# ProPrj_5VBuck_MP2236_2024-12-14.net
KiCad netlist of a schematic drawn in EasyEDA Pro
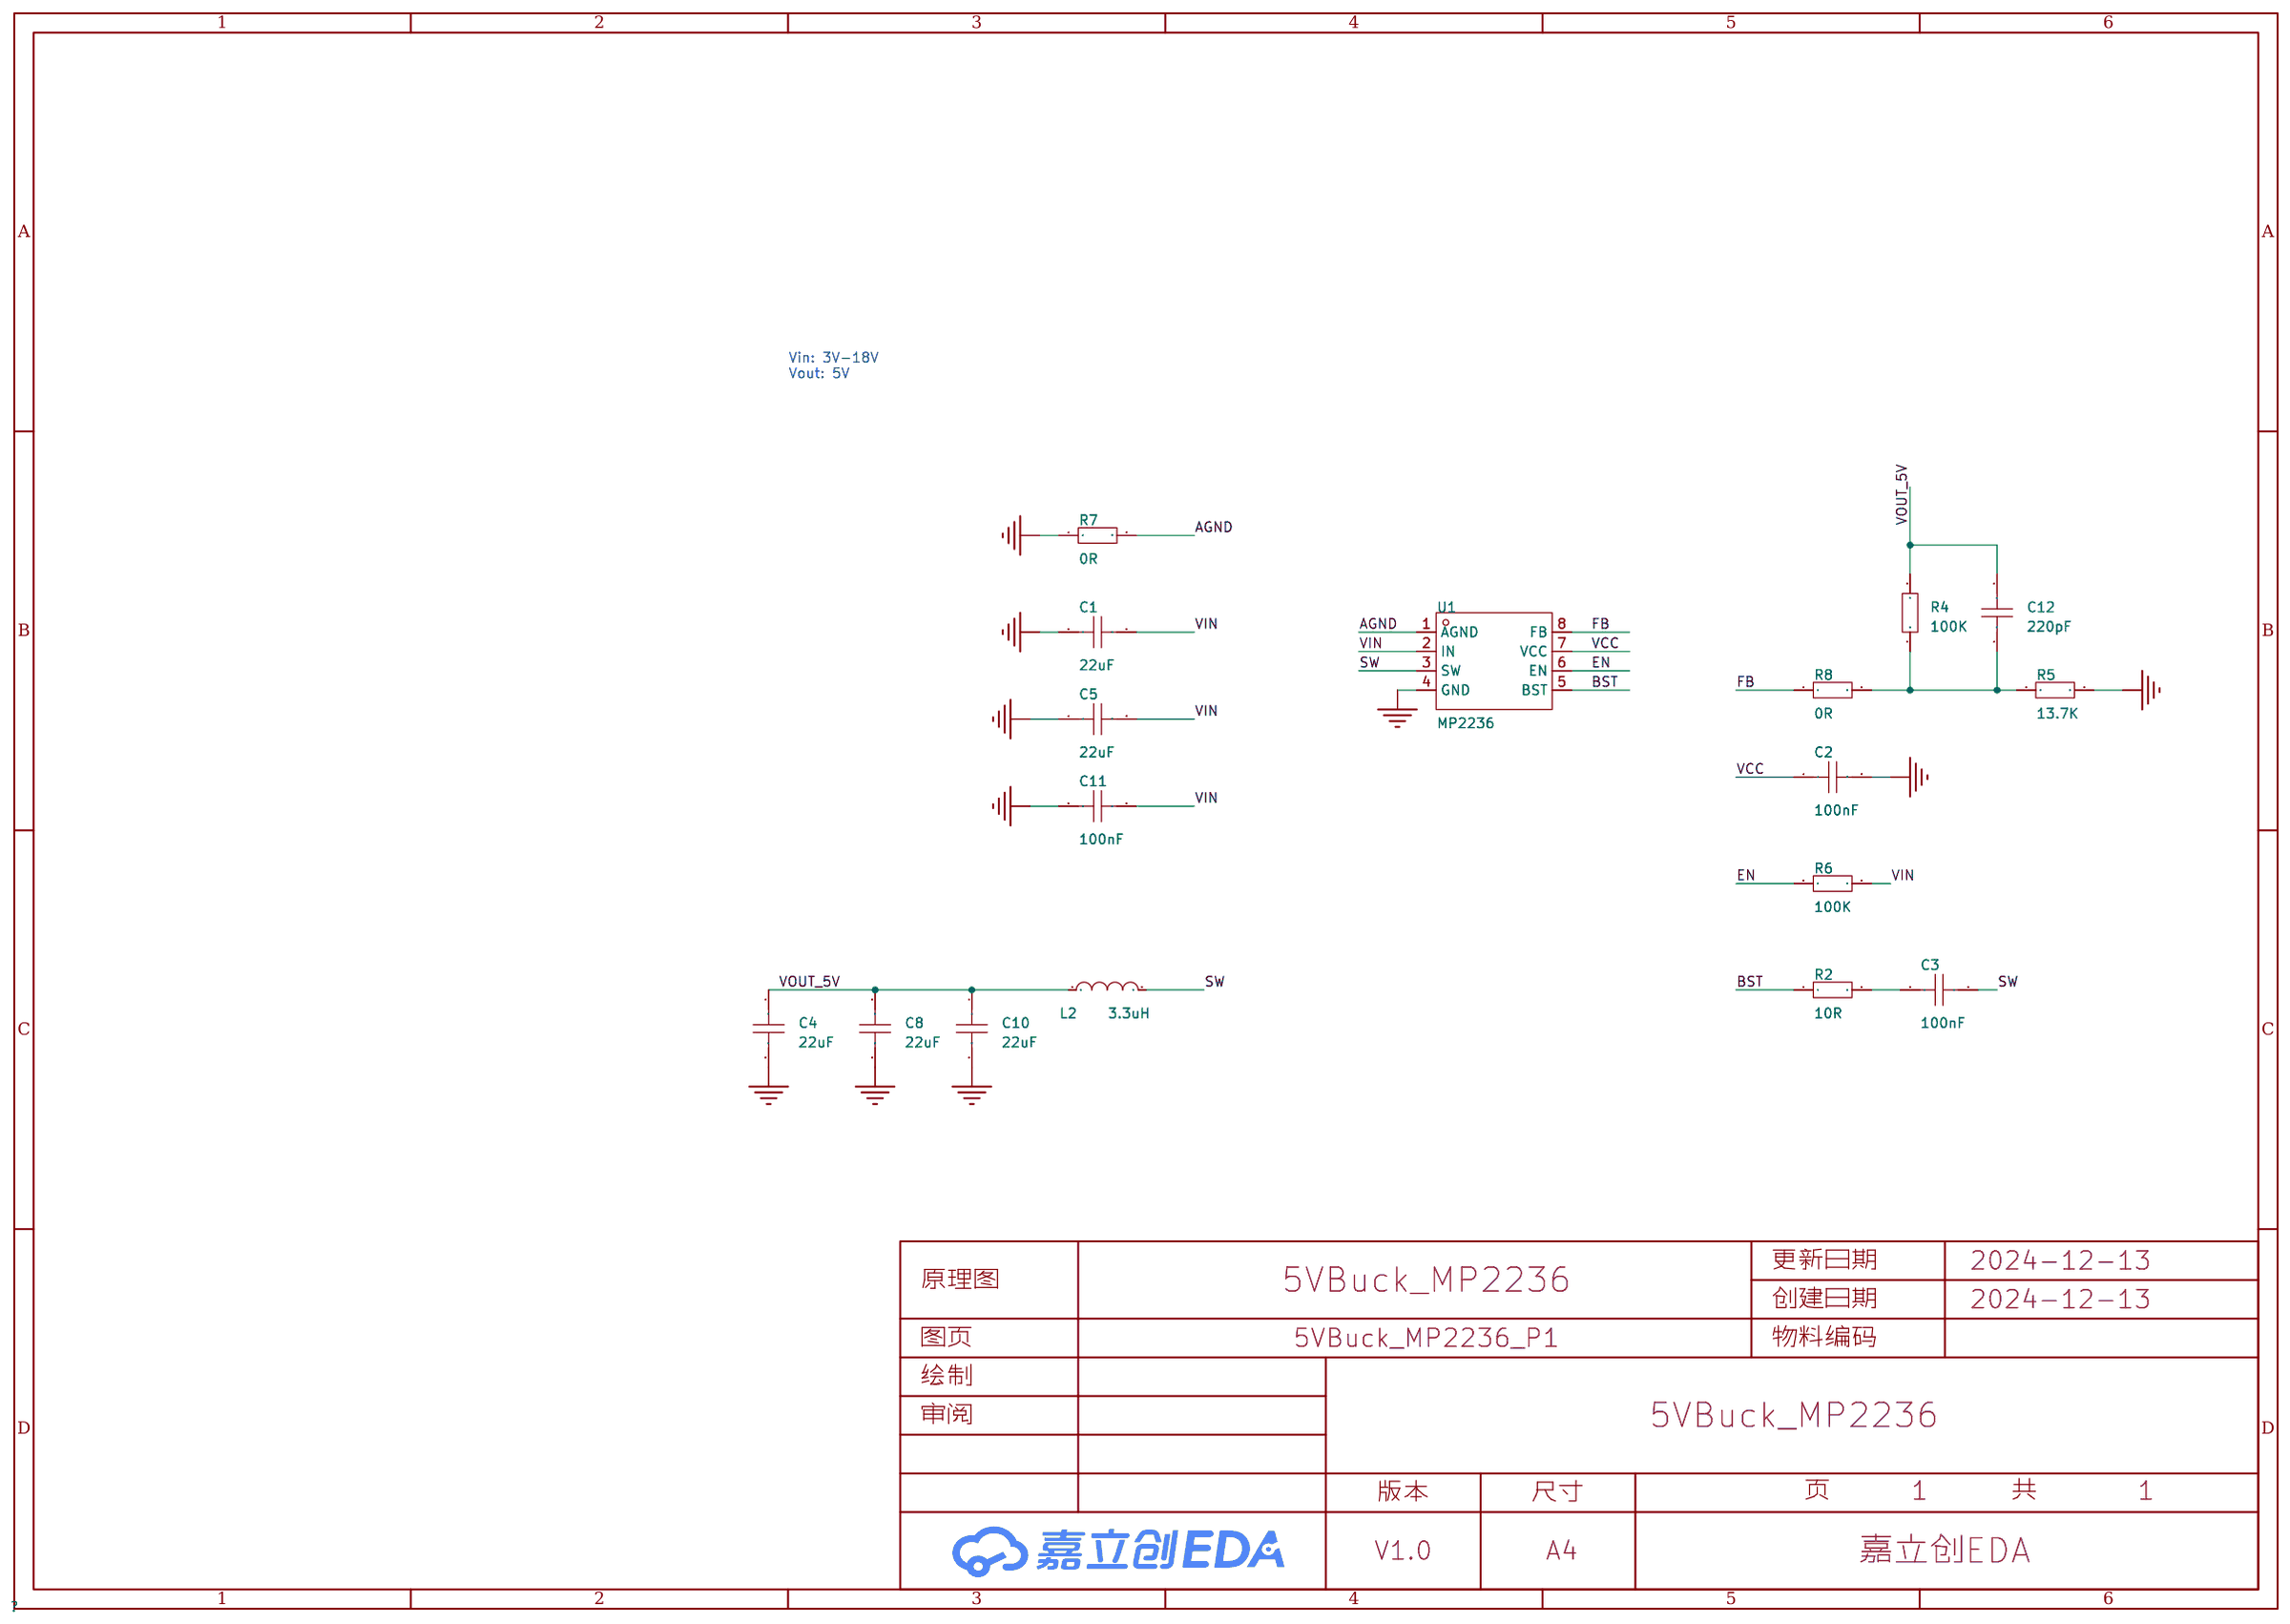
[diagram p0: schematic sheet]

(export (version "E")
  (design (tool "Eeschema 10.0.6"))
  (components
    (comp (ref "C1")
      (value "22uF")
      (footprint "easyedapro:C0805")
      (libsource (lib "easyedapro") (part "CapAcitance"))
    )
    (comp (ref "C2")
      (value "100nF")
      (footprint "easyedapro:C0805")
      (libsource (lib "easyedapro") (part "CapAcitance"))
    )
    (comp (ref "C3")
      (value "100nF")
      (footprint "easyedapro:C0805")
      (libsource (lib "easyedapro") (part "CapAcitance"))
    )
    (comp (ref "C4")
      (value "22uF")
      (footprint "easyedapro:C0805")
      (libsource (lib "easyedapro") (part "CapAcitance"))
    )
    (comp (ref "C5")
      (value "22uF")
      (footprint "easyedapro:C0805")
      (libsource (lib "easyedapro") (part "CapAcitance"))
    )
    (comp (ref "C8")
      (value "22uF")
      (footprint "easyedapro:C0805")
      (libsource (lib "easyedapro") (part "CapAcitance"))
    )
    (comp (ref "C10")
      (value "22uF")
      (footprint "easyedapro:C0805")
      (libsource (lib "easyedapro") (part "CapAcitance"))
    )
    (comp (ref "C11")
      (value "100nF")
      (footprint "easyedapro:C0805")
      (libsource (lib "easyedapro") (part "CapAcitance"))
    )
    (comp (ref "C12")
      (value "220pF")
      (footprint "easyedapro:C0805")
      (libsource (lib "easyedapro") (part "CapAcitance"))
    )
    (comp (ref "L2")
      (value "3.3uH")
      (footprint "easyedapro:IND-SMD_L7.1-W6.6_MJC-0603T")
      (description "电感值:5.6uH;精度:±20%;额定电流:5.5A;饱和电流(Isat):7A;类型:一体成型电感;")
      (fields
        (field (name "Manufacturer Part") "CXP0630-5R6M-AG(5.6uh)")
        (field (name "Manufacturer") "DMBJ(振宝佳)")
      )
      (libsource (lib "easyedapro") (part "CXP0630-5R6M-AG(5.6UH)"))
    )
    (comp (ref "R2") (value "10R") (footprint "easyedapro:R0805") (libsource (lib "easyedapro") (part "电阻")))
    (comp (ref "R4") (value "100K") (footprint "easyedapro:R0805") (libsource (lib "easyedapro") (part "电阻")))
    (comp (ref "R5")
      (value "13.7K")
      (footprint "easyedapro:R0805")
      (libsource (lib "easyedapro") (part "电阻"))
    )
    (comp (ref "R6") (value "100K") (footprint "easyedapro:R0805") (libsource (lib "easyedapro") (part "电阻")))
    (comp (ref "R7") (value "0R") (footprint "easyedapro:R0805") (libsource (lib "easyedapro") (part "电阻")))
    (comp (ref "R8") (value "0R") (footprint "easyedapro:R0805") (libsource (lib "easyedapro") (part "电阻")))
    (comp (ref "U1")
      (value "MP2236")
      (footprint "easyedapro:SOT-23-8_L3.0-W1.7-P0.65-LS2.8-BL")
      (libsource (lib "easyedapro") (part "MP2236"))
    )
  )
  (nets
    (net (code "1") (name "/AGND") (class "Default")
      (node (ref "R7") (pin "2") (pinfunction "2_2") (pintype "input"))
      (node (ref "U1") (pin "1") (pinfunction "AGND_1") (pintype "unspecified"))
    )
    (net (code "2") (name "/BST") (class "Default")
      (node (ref "R2") (pin "1") (pinfunction "1_1") (pintype "input"))
      (node (ref "U1") (pin "5") (pinfunction "BST_5") (pintype "unspecified"))
    )
    (net (code "3") (name "/EN") (class "Default")
      (node (ref "R6") (pin "2") (pinfunction "2_2") (pintype "input"))
      (node (ref "U1") (pin "6") (pinfunction "EN_6") (pintype "unspecified"))
    )
    (net (code "4") (name "/FB") (class "Default")
      (node (ref "R8") (pin "1") (pinfunction "1_1") (pintype "input"))
      (node (ref "U1") (pin "8") (pinfunction "FB_8") (pintype "unspecified"))
    )
    (net (code "5") (name "/SW") (class "Default")
      (node (ref "C3") (pin "2") (pinfunction "2_2") (pintype "input"))
      (node (ref "L2") (pin "2") (pinfunction "2_2") (pintype "unspecified"))
      (node (ref "U1") (pin "3") (pinfunction "SW_3") (pintype "unspecified"))
    )
    (net (code "6") (name "/VCC") (class "Default")
      (node (ref "C2") (pin "1") (pinfunction "1_1") (pintype "input"))
      (node (ref "U1") (pin "7") (pinfunction "VCC_7") (pintype "unspecified"))
    )
    (net (code "7") (name "/VIN") (class "Default")
      (node (ref "C1") (pin "2") (pinfunction "2_2") (pintype "input"))
      (node (ref "C11") (pin "2") (pinfunction "2_2") (pintype "input"))
      (node (ref "C5") (pin "2") (pinfunction "2_2") (pintype "input"))
      (node (ref "R6") (pin "1") (pinfunction "1_1") (pintype "input"))
      (node (ref "U1") (pin "2") (pinfunction "IN_2") (pintype "unspecified"))
    )
    (net (code "8") (name "/VOUT_5V") (class "Default")
      (node (ref "C10") (pin "1") (pinfunction "1_1") (pintype "input"))
      (node (ref "C12") (pin "2") (pinfunction "2_2") (pintype "input"))
      (node (ref "C4") (pin "1") (pinfunction "1_1") (pintype "input"))
      (node (ref "C8") (pin "1") (pinfunction "1_1") (pintype "input"))
      (node (ref "L2") (pin "1") (pinfunction "1_1") (pintype "unspecified"))
      (node (ref "R4") (pin "2") (pinfunction "2_2") (pintype "input"))
    )
    (net (code "9") (name "GND") (class "Default")
      (node (ref "C1") (pin "1") (pinfunction "1_1") (pintype "input"))
      (node (ref "C10") (pin "2") (pinfunction "2_2") (pintype "input"))
      (node (ref "C11") (pin "1") (pinfunction "1_1") (pintype "input"))
      (node (ref "C2") (pin "2") (pinfunction "2_2") (pintype "input"))
      (node (ref "C4") (pin "2") (pinfunction "2_2") (pintype "input"))
      (node (ref "C5") (pin "1") (pinfunction "1_1") (pintype "input"))
      (node (ref "C8") (pin "2") (pinfunction "2_2") (pintype "input"))
      (node (ref "R5") (pin "2") (pinfunction "2_2") (pintype "input"))
      (node (ref "R7") (pin "1") (pinfunction "1_1") (pintype "input"))
      (node (ref "U1") (pin "4") (pinfunction "GND_4") (pintype "unspecified"))
    )
    (net (code "10") (name "Net-(C3-Pad1)") (class "Default")
      (node (ref "C3") (pin "1") (pinfunction "1_1") (pintype "input"))
      (node (ref "R2") (pin "2") (pinfunction "2_2") (pintype "input"))
    )
    (net (code "11") (name "Net-(C12-Pad1)") (class "Default")
      (node (ref "C12") (pin "1") (pinfunction "1_1") (pintype "input"))
      (node (ref "R4") (pin "1") (pinfunction "1_1") (pintype "input"))
      (node (ref "R5") (pin "1") (pinfunction "1_1") (pintype "input"))
      (node (ref "R8") (pin "2") (pinfunction "2_2") (pintype "input"))
    )
  )
)
